# THS788_2.net
KiCad netlist of a schematic drawn in Altium Designer
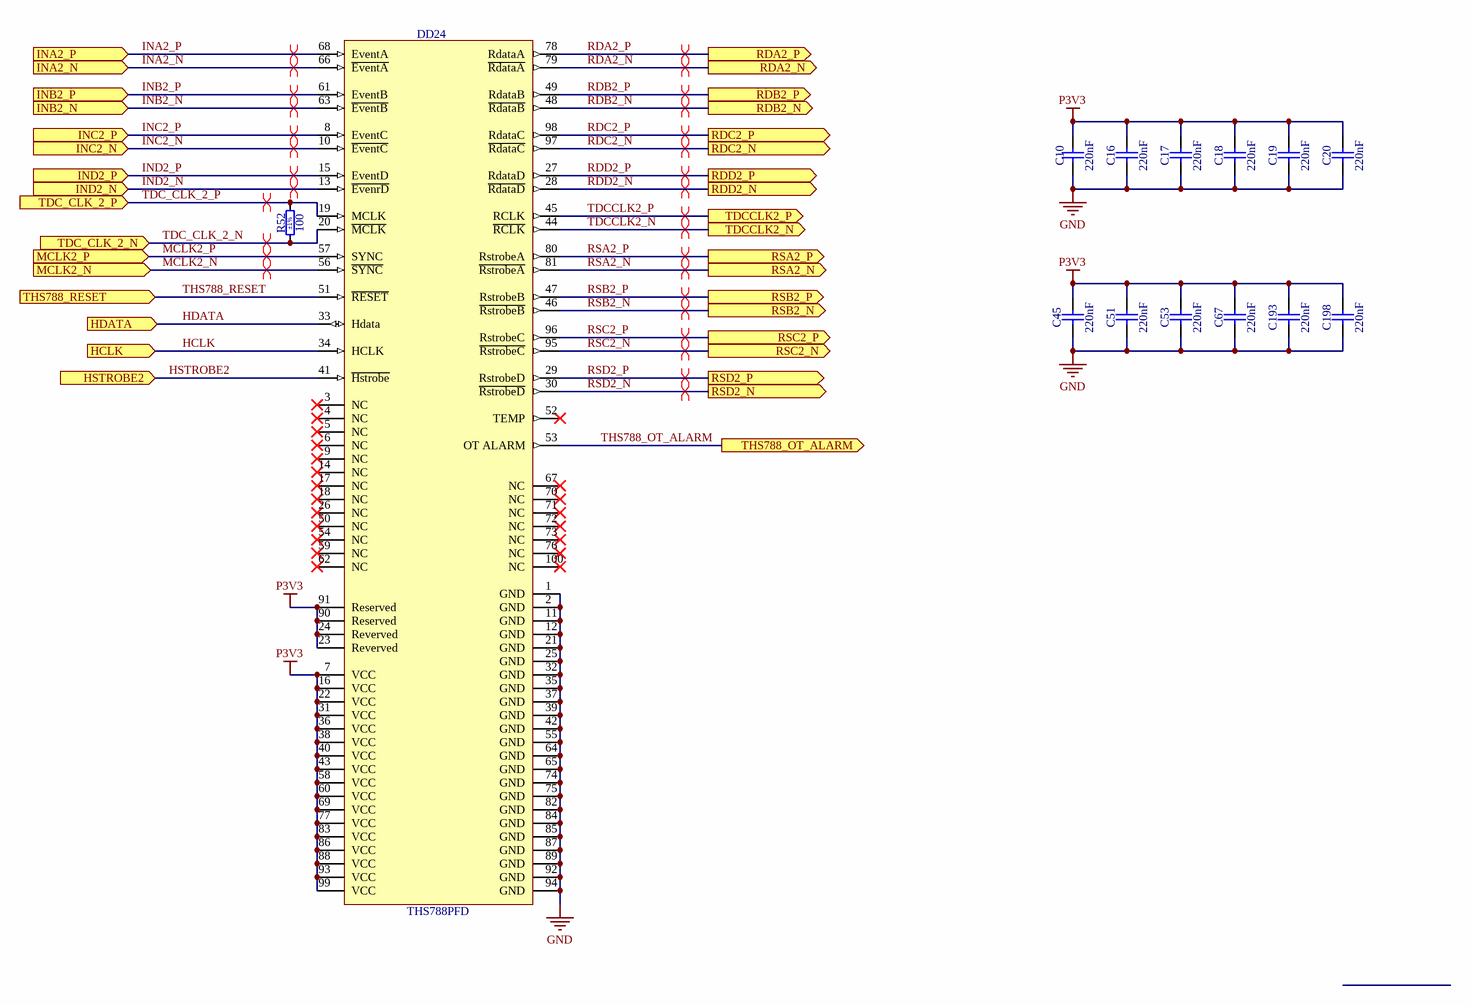
[diagram p0: THS788_2.SchDoc]

(export (version "E")
  (design (tool "Eeschema 10.0.6"))
  (components
    (comp (ref "C10")
      (value "220nF")
      (footprint "CAPC2012X135N")
      (description "Non-polarised capacitor")
      (fields
        (field (name "PART NUMBER") "CC0805_220NF_50V_10%_X7R")
        (field (name "VOLTAGE") "50V")
        (field (name "AUTHOR") "CERN DEM JLC")
      )
      (libsource (lib "Capacitors") (part "Capacitor - non polarized"))
    )
    (comp (ref "C16")
      (value "220nF")
      (footprint "CAPC2012X135N")
      (description "Non-polarised capacitor")
      (fields
        (field (name "PART NUMBER") "CC0805_220NF_50V_10%_X7R")
        (field (name "VOLTAGE") "50V")
        (field (name "AUTHOR") "CERN DEM JLC")
      )
      (libsource (lib "Capacitors") (part "Capacitor - non polarized"))
    )
    (comp (ref "C17")
      (value "220nF")
      (footprint "CAPC2012X135N")
      (description "Non-polarised capacitor")
      (fields
        (field (name "PART NUMBER") "CC0805_220NF_50V_10%_X7R")
        (field (name "VOLTAGE") "50V")
        (field (name "AUTHOR") "CERN DEM JLC")
      )
      (libsource (lib "Capacitors") (part "Capacitor - non polarized"))
    )
    (comp (ref "C18")
      (value "220nF")
      (footprint "CAPC2012X135N")
      (description "Non-polarised capacitor")
      (fields
        (field (name "PART NUMBER") "CC0805_220NF_50V_10%_X7R")
        (field (name "VOLTAGE") "50V")
        (field (name "AUTHOR") "CERN DEM JLC")
      )
      (libsource (lib "Capacitors") (part "Capacitor - non polarized"))
    )
    (comp (ref "C19")
      (value "220nF")
      (footprint "CAPC2012X135N")
      (description "Non-polarised capacitor")
      (fields
        (field (name "PART NUMBER") "CC0805_220NF_50V_10%_X7R")
        (field (name "VOLTAGE") "50V")
        (field (name "AUTHOR") "CERN DEM JLC")
      )
      (libsource (lib "Capacitors") (part "Capacitor - non polarized"))
    )
    (comp (ref "C20")
      (value "220nF")
      (footprint "CAPC2012X135N")
      (description "Non-polarised capacitor")
      (fields
        (field (name "PART NUMBER") "CC0805_220NF_50V_10%_X7R")
        (field (name "VOLTAGE") "50V")
        (field (name "AUTHOR") "CERN DEM JLC")
      )
      (libsource (lib "Capacitors") (part "Capacitor - non polarized"))
    )
    (comp (ref "C45")
      (value "220nF")
      (footprint "CAPC2012X135N")
      (description "Non-polarised capacitor")
      (fields
        (field (name "PART NUMBER") "CC0805_220NF_50V_10%_X7R")
        (field (name "VOLTAGE") "50V")
        (field (name "AUTHOR") "CERN DEM JLC")
      )
      (libsource (lib "Capacitors") (part "Capacitor - non polarized"))
    )
    (comp (ref "C51")
      (value "220nF")
      (footprint "CAPC2012X135N")
      (description "Non-polarised capacitor")
      (fields
        (field (name "PART NUMBER") "CC0805_220NF_50V_10%_X7R")
        (field (name "VOLTAGE") "50V")
        (field (name "AUTHOR") "CERN DEM JLC")
      )
      (libsource (lib "Capacitors") (part "Capacitor - non polarized"))
    )
    (comp (ref "C53")
      (value "220nF")
      (footprint "CAPC2012X135N")
      (description "Non-polarised capacitor")
      (fields
        (field (name "PART NUMBER") "CC0805_220NF_50V_10%_X7R")
        (field (name "VOLTAGE") "50V")
        (field (name "AUTHOR") "CERN DEM JLC")
      )
      (libsource (lib "Capacitors") (part "Capacitor - non polarized"))
    )
    (comp (ref "C67")
      (value "220nF")
      (footprint "CAPC2012X135N")
      (description "Non-polarised capacitor")
      (fields
        (field (name "PART NUMBER") "CC0805_220NF_50V_10%_X7R")
        (field (name "VOLTAGE") "50V")
        (field (name "AUTHOR") "CERN DEM JLC")
      )
      (libsource (lib "Capacitors") (part "Capacitor - non polarized"))
    )
    (comp (ref "C193")
      (value "220nF")
      (footprint "CAPC2012X135N")
      (description "Non-polarised capacitor")
      (fields
        (field (name "PART NUMBER") "CC0805_220NF_50V_10%_X7R")
        (field (name "VOLTAGE") "50V")
        (field (name "AUTHOR") "CERN DEM JLC")
      )
      (libsource (lib "Capacitors") (part "Capacitor - non polarized"))
    )
    (comp (ref "C198")
      (value "220nF")
      (footprint "CAPC2012X135N")
      (description "Non-polarised capacitor")
      (fields
        (field (name "PART NUMBER") "CC0805_220NF_50V_10%_X7R")
        (field (name "VOLTAGE") "50V")
        (field (name "AUTHOR") "CERN DEM JLC")
      )
      (libsource (lib "Capacitors") (part "Capacitor - non polarized"))
    )
    (comp (ref "DD24")
      (value "THS788PFD")
      (footprint "TEXAS_PFD (S-PQFP-G100)")
      (description "Quad-Channel Time Measurement Unit (TMU)")
      (fields (field (name "MANUFACTURER") "TEXAS INSTRUMENTS") (field (name "AUTHOR") "CERN DEM HF"))
      (libsource (lib "ICs And Semiconductors") (part "THS788PFD"))
    )
    (comp (ref "R52")
      (value "100")
      (footprint "RESC1608X55N")
      (description "Resistor - 1%")
      (fields
        (field (name "TOLERANCE") "±1%")
        (field (name "PART NUMBER") "R0603_100R_1%_0.1W_100PPM")
        (field (name "POWER") "0.1W")
        (field (name "AUTHOR") "CERN DEM JLC")
      )
      (libsource (lib "Resistors") (part "Resistor - 1%"))
    )
  )
  (nets
    (net (code "1") (name "/HCLK") (class "Default")
      (node (ref "DD24") (pin "34") (pinfunction "HCLK_34") (pintype "input"))
    )
    (net (code "2") (name "/HDATA") (class "Default")
      (node (ref "DD24") (pin "33") (pinfunction "Hdata_33") (pintype "bidirectional"))
    )
    (net (code "3") (name "/HSTROBE2") (class "Default")
      (node (ref "DD24") (pin "41") (pinfunction "~{Hstrobe}_41") (pintype "input"))
    )
    (net (code "4") (name "/INA2_N") (class "Default")
      (node (ref "DD24") (pin "66") (pinfunction "~{EventA}_66") (pintype "input"))
    )
    (net (code "5") (name "/INA2_P") (class "Default")
      (node (ref "DD24") (pin "68") (pinfunction "EventA_68") (pintype "input"))
    )
    (net (code "6") (name "/INB2_N") (class "Default")
      (node (ref "DD24") (pin "63") (pinfunction "~{EventB}_63") (pintype "input"))
    )
    (net (code "7") (name "/INB2_P") (class "Default")
      (node (ref "DD24") (pin "61") (pinfunction "EventB_61") (pintype "input"))
    )
    (net (code "8") (name "/INC2_N") (class "Default")
      (node (ref "DD24") (pin "10") (pinfunction "~{EventC}_10") (pintype "input"))
    )
    (net (code "9") (name "/INC2_P") (class "Default")
      (node (ref "DD24") (pin "8") (pinfunction "EventC_8") (pintype "input"))
    )
    (net (code "10") (name "/IND2_N") (class "Default")
      (node (ref "DD24") (pin "13") (pinfunction "~{EvenrD}_13") (pintype "input"))
    )
    (net (code "11") (name "/IND2_P") (class "Default")
      (node (ref "DD24") (pin "15") (pinfunction "EventD_15") (pintype "input"))
    )
    (net (code "12") (name "/MCLK2_N") (class "Default")
      (node (ref "DD24") (pin "56") (pinfunction "~{SYNC}_56") (pintype "input"))
    )
    (net (code "13") (name "/MCLK2_P") (class "Default")
      (node (ref "DD24") (pin "57") (pinfunction "SYNC_57") (pintype "input"))
    )
    (net (code "14") (name "/RDA2_N") (class "Default")
      (node (ref "DD24") (pin "79") (pinfunction "~{RdataA}_79") (pintype "output"))
    )
    (net (code "15") (name "/RDA2_P") (class "Default")
      (node (ref "DD24") (pin "78") (pinfunction "RdataA_78") (pintype "output"))
    )
    (net (code "16") (name "/RDB2_N") (class "Default")
      (node (ref "DD24") (pin "48") (pinfunction "~{RdataB}_48") (pintype "output"))
    )
    (net (code "17") (name "/RDB2_P") (class "Default")
      (node (ref "DD24") (pin "49") (pinfunction "RdataB_49") (pintype "output"))
    )
    (net (code "18") (name "/RDC2_N") (class "Default")
      (node (ref "DD24") (pin "97") (pinfunction "~{RdataC}_97") (pintype "output"))
    )
    (net (code "19") (name "/RDC2_P") (class "Default")
      (node (ref "DD24") (pin "98") (pinfunction "RdataC_98") (pintype "output"))
    )
    (net (code "20") (name "/RDD2_N") (class "Default")
      (node (ref "DD24") (pin "28") (pinfunction "~{RdataD}_28") (pintype "output"))
    )
    (net (code "21") (name "/RDD2_P") (class "Default")
      (node (ref "DD24") (pin "27") (pinfunction "RdataD_27") (pintype "output"))
    )
    (net (code "22") (name "/RSA2_N") (class "Default")
      (node (ref "DD24") (pin "81") (pinfunction "~{RstrobeA}_81") (pintype "output"))
    )
    (net (code "23") (name "/RSA2_P") (class "Default")
      (node (ref "DD24") (pin "80") (pinfunction "RstrobeA_80") (pintype "output"))
    )
    (net (code "24") (name "/RSB2_N") (class "Default")
      (node (ref "DD24") (pin "46") (pinfunction "~{RstrobeB}_46") (pintype "output"))
    )
    (net (code "25") (name "/RSB2_P") (class "Default")
      (node (ref "DD24") (pin "47") (pinfunction "RstrobeB_47") (pintype "output"))
    )
    (net (code "26") (name "/RSC2_N") (class "Default")
      (node (ref "DD24") (pin "95") (pinfunction "~{RstrobeC}_95") (pintype "output"))
    )
    (net (code "27") (name "/RSC2_P") (class "Default")
      (node (ref "DD24") (pin "96") (pinfunction "RstrobeC_96") (pintype "output"))
    )
    (net (code "28") (name "/RSD2_N") (class "Default")
      (node (ref "DD24") (pin "30") (pinfunction "~{RstrobeD}_30") (pintype "output"))
    )
    (net (code "29") (name "/RSD2_P") (class "Default")
      (node (ref "DD24") (pin "29") (pinfunction "RstrobeD_29") (pintype "output"))
    )
    (net (code "30") (name "/TDCCLK2_N") (class "Default")
      (node (ref "DD24") (pin "44") (pinfunction "~{RCLK}_44") (pintype "output"))
    )
    (net (code "31") (name "/TDCCLK2_P") (class "Default")
      (node (ref "DD24") (pin "45") (pinfunction "RCLK_45") (pintype "output"))
    )
    (net (code "32") (name "/TDC_CLK_2_N") (class "Default")
      (node (ref "DD24") (pin "20") (pinfunction "~{MCLK}_20") (pintype "input"))
      (node (ref "R52") (pin "1") (pinfunction "1_1") (pintype "passive"))
    )
    (net (code "33") (name "/TDC_CLK_2_P") (class "Default")
      (node (ref "DD24") (pin "19") (pinfunction "MCLK_19") (pintype "input"))
      (node (ref "R52") (pin "2") (pinfunction "2_2") (pintype "passive"))
    )
    (net (code "34") (name "/THS788_OT_ALARM") (class "Default")
      (node (ref "DD24") (pin "53") (pinfunction "OT_ALARM_53") (pintype "output"))
    )
    (net (code "35") (name "/THS788_RESET") (class "Default")
      (node (ref "DD24") (pin "51") (pinfunction "~{RESET}_51") (pintype "input"))
    )
    (net (code "36") (name "GND") (class "Default")
      (node (ref "C10") (pin "1") (pinfunction "1_1") (pintype "passive"))
      (node (ref "C16") (pin "1") (pinfunction "1_1") (pintype "passive"))
      (node (ref "C17") (pin "1") (pinfunction "1_1") (pintype "passive"))
      (node (ref "C18") (pin "1") (pinfunction "1_1") (pintype "passive"))
      (node (ref "C19") (pin "1") (pinfunction "1_1") (pintype "passive"))
      (node (ref "C193") (pin "1") (pinfunction "1_1") (pintype "passive"))
      (node (ref "C198") (pin "1") (pinfunction "1_1") (pintype "passive"))
      (node (ref "C20") (pin "1") (pinfunction "1_1") (pintype "passive"))
      (node (ref "C45") (pin "1") (pinfunction "1_1") (pintype "passive"))
      (node (ref "C51") (pin "1") (pinfunction "1_1") (pintype "passive"))
      (node (ref "C53") (pin "1") (pinfunction "1_1") (pintype "passive"))
      (node (ref "C67") (pin "1") (pinfunction "1_1") (pintype "passive"))
      (node (ref "DD24") (pin "1") (pinfunction "GND_1") (pintype "power_in"))
      (node (ref "DD24") (pin "11") (pinfunction "GND_11") (pintype "power_in"))
      (node (ref "DD24") (pin "12") (pinfunction "GND_12") (pintype "power_in"))
      (node (ref "DD24") (pin "2") (pinfunction "GND_2") (pintype "power_in"))
      (node (ref "DD24") (pin "21") (pinfunction "GND_21") (pintype "power_in"))
      (node (ref "DD24") (pin "25") (pinfunction "GND_25") (pintype "power_in"))
      (node (ref "DD24") (pin "32") (pinfunction "GND_32") (pintype "power_in"))
      (node (ref "DD24") (pin "35") (pinfunction "GND_35") (pintype "power_in"))
      (node (ref "DD24") (pin "37") (pinfunction "GND_37") (pintype "power_in"))
      (node (ref "DD24") (pin "39") (pinfunction "GND_39") (pintype "power_in"))
      (node (ref "DD24") (pin "42") (pinfunction "GND_42") (pintype "power_in"))
      (node (ref "DD24") (pin "55") (pinfunction "GND_55") (pintype "power_in"))
      (node (ref "DD24") (pin "64") (pinfunction "GND_64") (pintype "power_in"))
      (node (ref "DD24") (pin "65") (pinfunction "GND_65") (pintype "power_in"))
      (node (ref "DD24") (pin "74") (pinfunction "GND_74") (pintype "power_in"))
      (node (ref "DD24") (pin "75") (pinfunction "GND_75") (pintype "power_in"))
      (node (ref "DD24") (pin "82") (pinfunction "GND_82") (pintype "power_in"))
      (node (ref "DD24") (pin "84") (pinfunction "GND_84") (pintype "power_in"))
      (node (ref "DD24") (pin "85") (pinfunction "GND_85") (pintype "power_in"))
      (node (ref "DD24") (pin "87") (pinfunction "GND_87") (pintype "power_in"))
      (node (ref "DD24") (pin "89") (pinfunction "GND_89") (pintype "power_in"))
      (node (ref "DD24") (pin "92") (pinfunction "GND_92") (pintype "power_in"))
      (node (ref "DD24") (pin "94") (pinfunction "GND_94") (pintype "power_in"))
    )
    (net (code "37") (name "P3V3") (class "Default")
      (node (ref "C10") (pin "2") (pinfunction "2_2") (pintype "passive"))
      (node (ref "C16") (pin "2") (pinfunction "2_2") (pintype "passive"))
      (node (ref "C17") (pin "2") (pinfunction "2_2") (pintype "passive"))
      (node (ref "C18") (pin "2") (pinfunction "2_2") (pintype "passive"))
      (node (ref "C19") (pin "2") (pinfunction "2_2") (pintype "passive"))
      (node (ref "C193") (pin "2") (pinfunction "2_2") (pintype "passive"))
      (node (ref "C198") (pin "2") (pinfunction "2_2") (pintype "passive"))
      (node (ref "C20") (pin "2") (pinfunction "2_2") (pintype "passive"))
      (node (ref "C45") (pin "2") (pinfunction "2_2") (pintype "passive"))
      (node (ref "C51") (pin "2") (pinfunction "2_2") (pintype "passive"))
      (node (ref "C53") (pin "2") (pinfunction "2_2") (pintype "passive"))
      (node (ref "C67") (pin "2") (pinfunction "2_2") (pintype "passive"))
      (node (ref "DD24") (pin "16") (pinfunction "VCC_16") (pintype "power_in"))
      (node (ref "DD24") (pin "22") (pinfunction "VCC_22") (pintype "power_in"))
      (node (ref "DD24") (pin "23") (pinfunction "Reverved_23") (pintype "passive"))
      (node (ref "DD24") (pin "24") (pinfunction "Reverved_24") (pintype "passive"))
      (node (ref "DD24") (pin "31") (pinfunction "VCC_31") (pintype "power_in"))
      (node (ref "DD24") (pin "36") (pinfunction "VCC_36") (pintype "power_in"))
      (node (ref "DD24") (pin "38") (pinfunction "VCC_38") (pintype "power_in"))
      (node (ref "DD24") (pin "40") (pinfunction "VCC_40") (pintype "power_in"))
      (node (ref "DD24") (pin "43") (pinfunction "VCC_43") (pintype "power_in"))
      (node (ref "DD24") (pin "58") (pinfunction "VCC_58") (pintype "power_in"))
      (node (ref "DD24") (pin "60") (pinfunction "VCC_60") (pintype "power_in"))
      (node (ref "DD24") (pin "69") (pinfunction "VCC_69") (pintype "power_in"))
      (node (ref "DD24") (pin "7") (pinfunction "VCC_7") (pintype "power_in"))
      (node (ref "DD24") (pin "77") (pinfunction "VCC_77") (pintype "power_in"))
      (node (ref "DD24") (pin "83") (pinfunction "VCC_83") (pintype "power_in"))
      (node (ref "DD24") (pin "86") (pinfunction "VCC_86") (pintype "power_in"))
      (node (ref "DD24") (pin "88") (pinfunction "VCC_88") (pintype "power_in"))
      (node (ref "DD24") (pin "90") (pinfunction "Reserved_90") (pintype "passive"))
      (node (ref "DD24") (pin "91") (pinfunction "Reserved_91") (pintype "passive"))
      (node (ref "DD24") (pin "93") (pinfunction "VCC_93") (pintype "power_in"))
      (node (ref "DD24") (pin "99") (pinfunction "VCC_99") (pintype "power_in"))
    )
    (net (code "38") (name "unconnected-(DD24-NC-Pad3)") (class "Default")
      (node (ref "DD24") (pin "3") (pinfunction "NC_3") (pintype "passive+no_connect"))
    )
    (net (code "39") (name "unconnected-(DD24-NC-Pad4)") (class "Default")
      (node (ref "DD24") (pin "4") (pinfunction "NC_4") (pintype "passive+no_connect"))
    )
    (net (code "40") (name "unconnected-(DD24-NC-Pad5)") (class "Default")
      (node (ref "DD24") (pin "5") (pinfunction "NC_5") (pintype "passive+no_connect"))
    )
    (net (code "41") (name "unconnected-(DD24-NC-Pad6)") (class "Default")
      (node (ref "DD24") (pin "6") (pinfunction "NC_6") (pintype "passive+no_connect"))
    )
    (net (code "42") (name "unconnected-(DD24-NC-Pad9)") (class "Default")
      (node (ref "DD24") (pin "9") (pinfunction "NC_9") (pintype "passive+no_connect"))
    )
    (net (code "43") (name "unconnected-(DD24-NC-Pad14)") (class "Default")
      (node (ref "DD24") (pin "14") (pinfunction "NC_14") (pintype "passive+no_connect"))
    )
    (net (code "44") (name "unconnected-(DD24-NC-Pad17)") (class "Default")
      (node (ref "DD24") (pin "17") (pinfunction "NC_17") (pintype "passive+no_connect"))
    )
    (net (code "45") (name "unconnected-(DD24-NC-Pad18)") (class "Default")
      (node (ref "DD24") (pin "18") (pinfunction "NC_18") (pintype "passive+no_connect"))
    )
    (net (code "46") (name "unconnected-(DD24-NC-Pad26)") (class "Default")
      (node (ref "DD24") (pin "26") (pinfunction "NC_26") (pintype "passive+no_connect"))
    )
    (net (code "47") (name "unconnected-(DD24-NC-Pad50)") (class "Default")
      (node (ref "DD24") (pin "50") (pinfunction "NC_50") (pintype "passive+no_connect"))
    )
    (net (code "48") (name "unconnected-(DD24-NC-Pad54)") (class "Default")
      (node (ref "DD24") (pin "54") (pinfunction "NC_54") (pintype "passive+no_connect"))
    )
    (net (code "49") (name "unconnected-(DD24-NC-Pad59)") (class "Default")
      (node (ref "DD24") (pin "59") (pinfunction "NC_59") (pintype "passive+no_connect"))
    )
    (net (code "50") (name "unconnected-(DD24-NC-Pad62)") (class "Default")
      (node (ref "DD24") (pin "62") (pinfunction "NC_62") (pintype "passive+no_connect"))
    )
    (net (code "51") (name "unconnected-(DD24-NC-Pad67)") (class "Default")
      (node (ref "DD24") (pin "67") (pinfunction "NC_67") (pintype "passive+no_connect"))
    )
    (net (code "52") (name "unconnected-(DD24-NC-Pad70)") (class "Default")
      (node (ref "DD24") (pin "70") (pinfunction "NC_70") (pintype "passive+no_connect"))
    )
    (net (code "53") (name "unconnected-(DD24-NC-Pad71)") (class "Default")
      (node (ref "DD24") (pin "71") (pinfunction "NC_71") (pintype "passive+no_connect"))
    )
    (net (code "54") (name "unconnected-(DD24-NC-Pad72)") (class "Default")
      (node (ref "DD24") (pin "72") (pinfunction "NC_72") (pintype "passive+no_connect"))
    )
    (net (code "55") (name "unconnected-(DD24-NC-Pad73)") (class "Default")
      (node (ref "DD24") (pin "73") (pinfunction "NC_73") (pintype "passive+no_connect"))
    )
    (net (code "56") (name "unconnected-(DD24-NC-Pad76)") (class "Default")
      (node (ref "DD24") (pin "76") (pinfunction "NC_76") (pintype "passive+no_connect"))
    )
    (net (code "57") (name "unconnected-(DD24-NC-Pad100)") (class "Default")
      (node (ref "DD24") (pin "100") (pinfunction "NC_100") (pintype "passive+no_connect"))
    )
    (net (code "58") (name "unconnected-(DD24-TEMP-Pad52)") (class "Default")
      (node (ref "DD24") (pin "52") (pinfunction "TEMP_52") (pintype "output+no_connect"))
    )
  )
)
